# pcb4.net
KiCad netlist of a schematic drawn in EAGLE
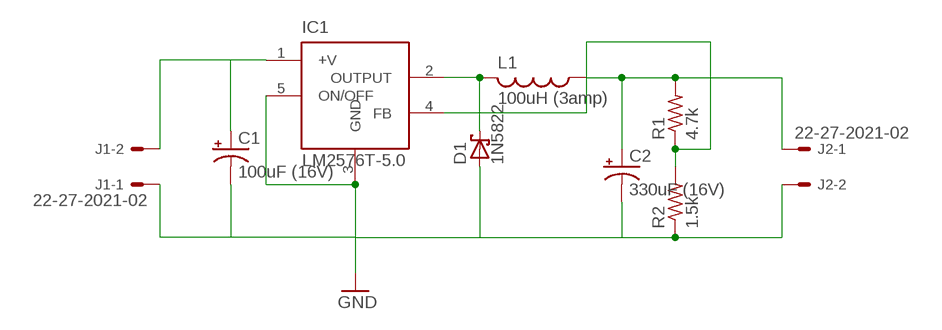
[diagram p0: schematic, sheet 1]

(export (version "E")
  (design (tool "Eeschema 10.0.6"))
  (components
    (comp (ref "C1")
      (value "100uF (16V)")
      (footprint "eagle-import:TT2D6")
      (libsource (lib "eagle-import") (part "CPOL-USTT2D6"))
    )
    (comp (ref "C2")
      (value "330uF (16V)")
      (footprint "eagle-import:TT5D10")
      (libsource (lib "eagle-import") (part "CPOL-USTT5D10"))
    )
    (comp (ref "D1")
      (value "1N5822")
      (footprint "eagle-import:C4111-15")
      (libsource (lib "eagle-import") (part "1N5908"))
    )
    (comp (ref "IC1")
      (value "LM2576T-5.0")
      (footprint "eagle-import:TO220-5")
      (libsource (lib "eagle-import") (part "LM2576T-5.0"))
    )
    (comp (ref "J1")
      (value "22-27-2021-02")
      (footprint "eagle-import:6410-02")
      (libsource (lib "eagle-import") (part "22-?-0227-2021"))
    )
    (comp (ref "J2")
      (value "22-27-2021-02")
      (footprint "eagle-import:6410-02")
      (libsource (lib "eagle-import") (part "22-?-0227-2021"))
    )
    (comp (ref "L1")
      (value "100uH (3amp)")
      (footprint "eagle-import:TJ3-U1")
      (libsource (lib "eagle-import") (part "L-USTJ3-U1"))
    )
    (comp (ref "R1")
      (value "4.7k")
      (footprint "eagle-import:0204_7")
      (libsource (lib "eagle-import") (part "R-US_0204/7"))
    )
    (comp (ref "R2")
      (value "1.5k")
      (footprint "eagle-import:0204_7")
      (libsource (lib "eagle-import") (part "R-US_0204/7"))
    )
  )
  (nets
    (net (code "1") (name "GND") (class "Default")
      (node (ref "C1") (pin "-") (pinfunction "-_-") (pintype "passive"))
      (node (ref "C2") (pin "-") (pinfunction "-_-") (pintype "passive"))
      (node (ref "D1") (pin "A") (pinfunction "A_A") (pintype "passive"))
      (node (ref "IC1") (pin "3") (pinfunction "GND_3") (pintype "power_in"))
      (node (ref "IC1") (pin "5") (pinfunction "ON/OFF_5") (pintype "input"))
      (node (ref "J1") (pin "1") (pinfunction "S_1") (pintype "passive"))
      (node (ref "J2") (pin "2") (pinfunction "S_2") (pintype "passive"))
      (node (ref "R2") (pin "1") (pinfunction "1_1") (pintype "passive"))
    )
    (net (code "2") (name "Net-(IC1-+V)") (class "Default")
      (node (ref "C1") (pin "+") (pinfunction "+_+") (pintype "passive"))
      (node (ref "IC1") (pin "1") (pinfunction "+V_1") (pintype "power_in"))
      (node (ref "J1") (pin "2") (pinfunction "S_2") (pintype "passive"))
    )
    (net (code "3") (name "Net-(IC1-FB)") (class "Default")
      (node (ref "IC1") (pin "4") (pinfunction "FB_4") (pintype "input"))
      (node (ref "R1") (pin "1") (pinfunction "1_1") (pintype "passive"))
      (node (ref "R2") (pin "2") (pinfunction "2_2") (pintype "passive"))
    )
    (net (code "4") (name "Net-(IC1-OUTPUT)") (class "Default")
      (node (ref "D1") (pin "C") (pinfunction "C_C") (pintype "passive"))
      (node (ref "IC1") (pin "2") (pinfunction "OUTPUT_2") (pintype "output"))
      (node (ref "L1") (pin "2") (pinfunction "2_2") (pintype "passive"))
    )
    (net (code "5") (name "Net-(J2A-S)") (class "Default")
      (node (ref "C2") (pin "+") (pinfunction "+_+") (pintype "passive"))
      (node (ref "J2") (pin "1") (pinfunction "S_1") (pintype "passive"))
      (node (ref "L1") (pin "1") (pinfunction "1_1") (pintype "passive"))
      (node (ref "R1") (pin "2") (pinfunction "2_2") (pintype "passive"))
    )
  )
)
